# 1_1.net
KiCad netlist of a schematic drawn in Altium Designer
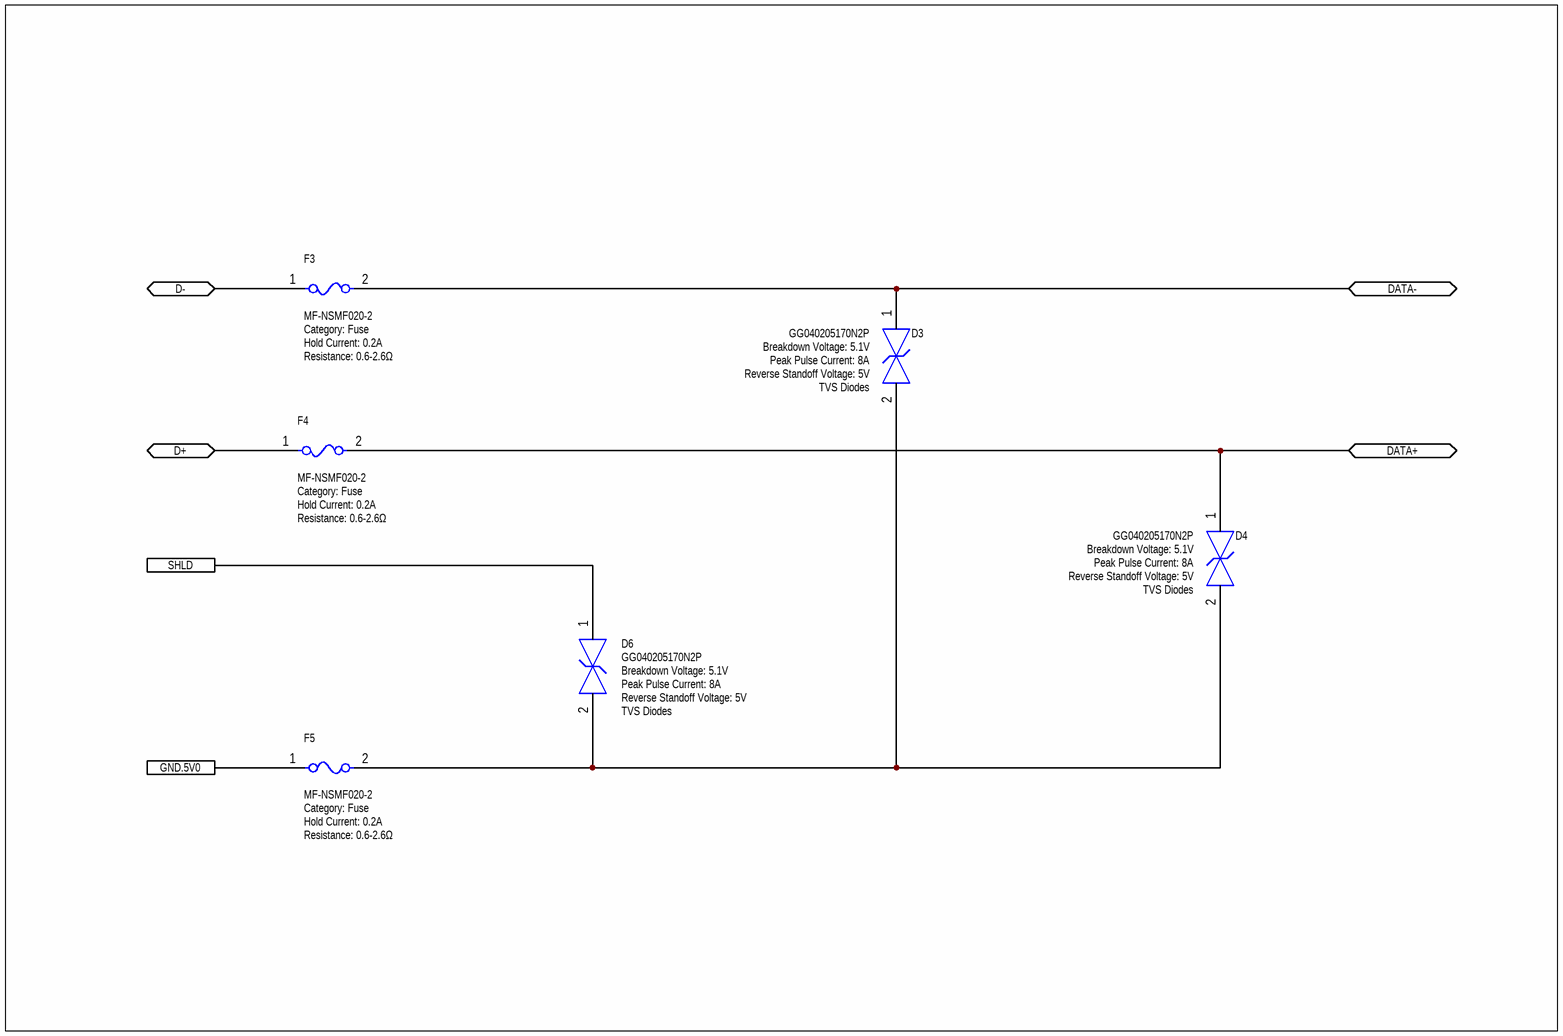
[diagram p0: Блок1.1.SchDoc]

(export (version "E")
  (design (tool "Eeschema 10.0.6"))
  (components
    (comp (ref "D3")
      (value "GG040205170N2P")
      (footprint "FP-GG0402-IPC_A")
      (description "TVS DIODE 5V 10V 0402")
      (fields
        (field (name "OCTOPART") "https://octopart.com/gg040205170n2p-avx-81066082")
        (field (name "MANUFACTURER") "AVX")
        (field (name "BREAKDOWN VOLTAGE") "5.1V")
        (field (name "PEAK PULSE CURRENT") "8A")
        (field (name "REVERSE STANDOFF VOLTAGE") "5V")
        (field (name "DEVICE CLASS L2") "TVS Diodes")
      )
      (libsource (lib "Altium Content Vault") (part "11bd9d59d340f0612179daf16ad9b72"))
    )
    (comp (ref "D4")
      (value "GG040205170N2P")
      (footprint "FP-GG0402-IPC_A")
      (description "TVS DIODE 5V 10V 0402")
      (fields
        (field (name "OCTOPART") "https://octopart.com/gg040205170n2p-avx-81066082")
        (field (name "MANUFACTURER") "AVX")
        (field (name "BREAKDOWN VOLTAGE") "5.1V")
        (field (name "PEAK PULSE CURRENT") "8A")
        (field (name "REVERSE STANDOFF VOLTAGE") "5V")
        (field (name "DEVICE CLASS L2") "TVS Diodes")
      )
      (libsource (lib "Altium Content Vault") (part "11bd9d59d340f0612179daf16ad9b72"))
    )
    (comp (ref "D6")
      (value "GG040205170N2P")
      (footprint "FP-GG0402-IPC_A")
      (description "TVS DIODE 5V 10V 0402")
      (fields
        (field (name "OCTOPART") "https://octopart.com/gg040205170n2p-avx-81066082")
        (field (name "MANUFACTURER") "AVX")
        (field (name "BREAKDOWN VOLTAGE") "5.1V")
        (field (name "PEAK PULSE CURRENT") "8A")
        (field (name "REVERSE STANDOFF VOLTAGE") "5V")
        (field (name "DEVICE CLASS L2") "TVS Diodes")
      )
      (libsource (lib "Altium Content Vault") (part "11bd9d59d340f0612179daf16ad9b72"))
    )
    (comp (ref "F3")
      (value "MF-NSMF020-2")
      (footprint "FP-MF-NSMF020-2-MFG")
      (description "PTC RESET FUSE 24V 200MA 1206")
      (fields
        (field (name "CATEGORY") "Fuse")
        (field (name "HOLD CURRENT") "0.2A")
        (field (name "MANUFACTURER") "Bourns")
        (field (name "OCTOPART") "https://octopart.com/mf-nsmf020-2-bourns-94649")
        (field (name "RESISTANCE") "0.6-2.6Ω")
      )
      (libsource (lib "Altium Content Vault") (part "5bcf9b9f640e542cf0359d10258e979"))
    )
    (comp (ref "F4")
      (value "MF-NSMF020-2")
      (footprint "FP-MF-NSMF020-2-MFG")
      (description "PTC RESET FUSE 24V 200MA 1206")
      (fields
        (field (name "CATEGORY") "Fuse")
        (field (name "HOLD CURRENT") "0.2A")
        (field (name "MANUFACTURER") "Bourns")
        (field (name "OCTOPART") "https://octopart.com/mf-nsmf020-2-bourns-94649")
        (field (name "RESISTANCE") "0.6-2.6Ω")
      )
      (libsource (lib "Altium Content Vault") (part "5bcf9b9f640e542cf0359d10258e979"))
    )
    (comp (ref "F5")
      (value "MF-NSMF020-2")
      (footprint "FP-MF-NSMF020-2-MFG")
      (description "PTC RESET FUSE 24V 200MA 1206")
      (fields
        (field (name "CATEGORY") "Fuse")
        (field (name "HOLD CURRENT") "0.2A")
        (field (name "MANUFACTURER") "Bourns")
        (field (name "OCTOPART") "https://octopart.com/mf-nsmf020-2-bourns-94649")
        (field (name "RESISTANCE") "0.6-2.6Ω")
      )
      (libsource (lib "Altium Content Vault") (part "5bcf9b9f640e542cf0359d10258e979"))
    )
  )
  (nets
    (net (code "1") (name "/D+") (class "Default")
      (node (ref "F4") (pin "1") (pinfunction "1_1") (pintype "passive"))
    )
    (net (code "2") (name "/D-") (class "Default")
      (node (ref "F3") (pin "1") (pinfunction "1_1") (pintype "passive"))
    )
    (net (code "3") (name "/DATA+") (class "Default")
      (node (ref "D4") (pin "1") (pinfunction "1_1") (pintype "passive"))
      (node (ref "F4") (pin "2") (pinfunction "2_2") (pintype "passive"))
    )
    (net (code "4") (name "/DATA-") (class "Default")
      (node (ref "D3") (pin "1") (pinfunction "1_1") (pintype "passive"))
      (node (ref "F3") (pin "2") (pinfunction "2_2") (pintype "passive"))
    )
    (net (code "5") (name "/GND.5V0") (class "Default")
      (node (ref "F5") (pin "1") (pinfunction "1_1") (pintype "passive"))
    )
    (net (code "6") (name "/SHLD") (class "Default")
      (node (ref "D6") (pin "1") (pinfunction "1_1") (pintype "passive"))
    )
    (net (code "7") (name "Net-(D3-Pad2)") (class "Default")
      (node (ref "D3") (pin "2") (pinfunction "2_2") (pintype "passive"))
      (node (ref "D4") (pin "2") (pinfunction "2_2") (pintype "passive"))
      (node (ref "D6") (pin "2") (pinfunction "2_2") (pintype "passive"))
      (node (ref "F5") (pin "2") (pinfunction "2_2") (pintype "passive"))
    )
  )
)
